# boardv2temperature.net
KiCad netlist of a schematic drawn in EAGLE
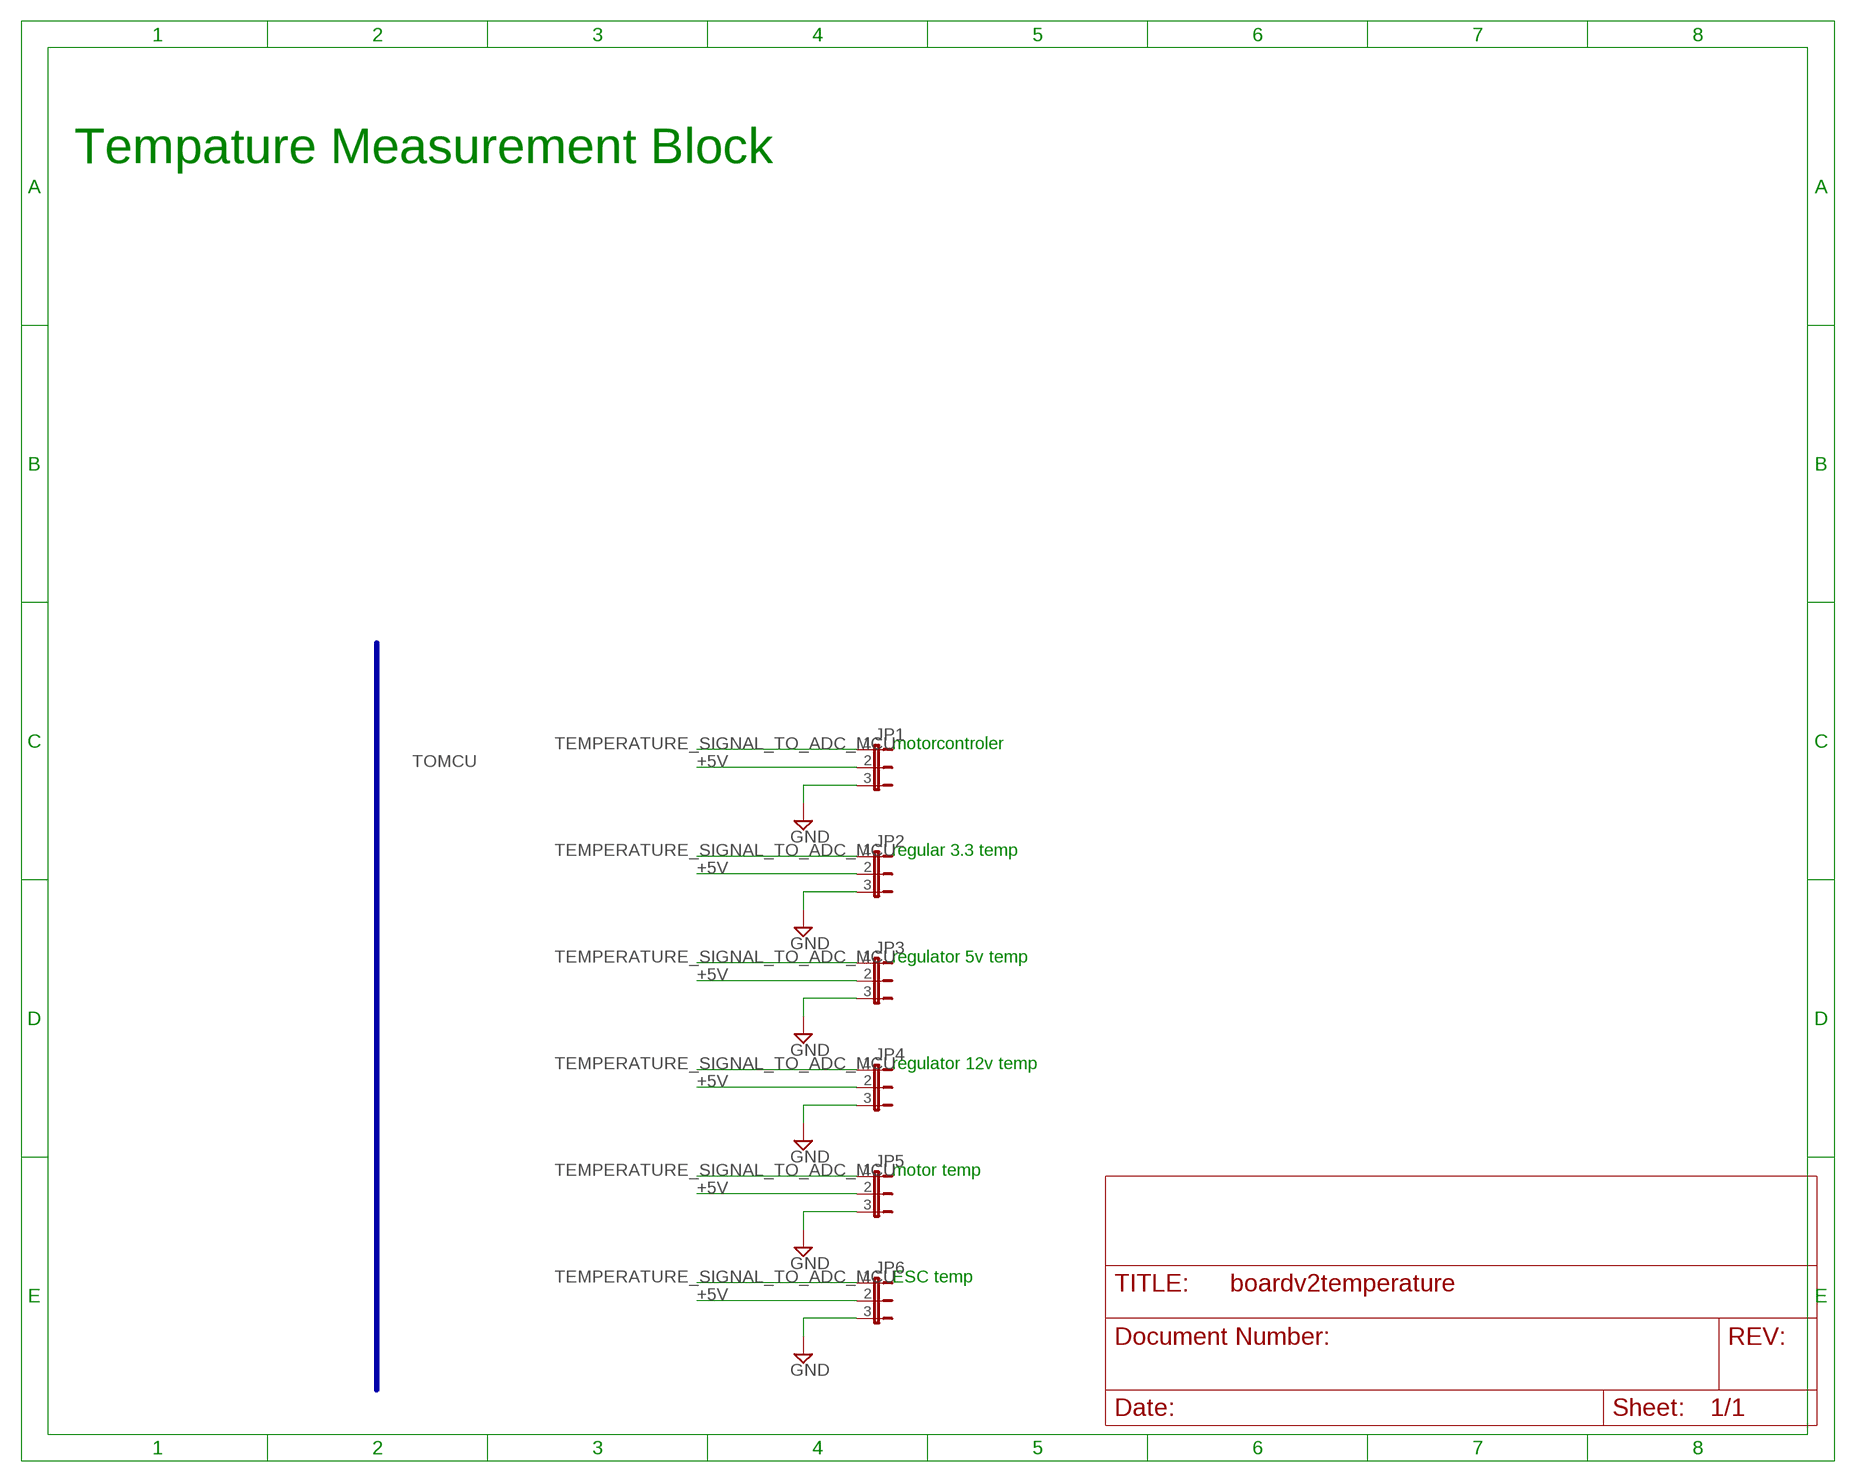
[diagram p0: schematic, sheet 1]

(export (version "E")
  (design (tool "Eeschema 10.0.6"))
  (components
    (comp (ref "JP1")
      (value "JP2E")
      (footprint "eagle-import:JP2")
      (libsource (lib "eagle-import") (part "JP2E"))
    )
    (comp (ref "JP2")
      (value "JP2E")
      (footprint "eagle-import:JP2")
      (libsource (lib "eagle-import") (part "JP2E"))
    )
    (comp (ref "JP3")
      (value "JP2E")
      (footprint "eagle-import:JP2")
      (libsource (lib "eagle-import") (part "JP2E"))
    )
    (comp (ref "JP4")
      (value "JP2E")
      (footprint "eagle-import:JP2")
      (libsource (lib "eagle-import") (part "JP2E"))
    )
    (comp (ref "JP5")
      (value "JP2E")
      (footprint "eagle-import:JP2")
      (libsource (lib "eagle-import") (part "JP2E"))
    )
    (comp (ref "JP6")
      (value "JP2E")
      (footprint "eagle-import:JP2")
      (libsource (lib "eagle-import") (part "JP2E"))
    )
  )
  (nets
    (net (code "2") (name "/+5V") (class "Default")
      (node (ref "JP1") (pin "2") (pinfunction "2_2") (pintype "passive"))
      (node (ref "JP2") (pin "2") (pinfunction "2_2") (pintype "passive"))
      (node (ref "JP3") (pin "2") (pinfunction "2_2") (pintype "passive"))
      (node (ref "JP4") (pin "2") (pinfunction "2_2") (pintype "passive"))
      (node (ref "JP5") (pin "2") (pinfunction "2_2") (pintype "passive"))
      (node (ref "JP6") (pin "2") (pinfunction "2_2") (pintype "passive"))
    )
    (net (code "3") (name "/TEMPERATURE_SIGNAL_TO_ADC_MCU") (class "Default")
      (node (ref "JP1") (pin "1") (pinfunction "1_1") (pintype "passive"))
      (node (ref "JP2") (pin "1") (pinfunction "1_1") (pintype "passive"))
      (node (ref "JP3") (pin "1") (pinfunction "1_1") (pintype "passive"))
      (node (ref "JP4") (pin "1") (pinfunction "1_1") (pintype "passive"))
      (node (ref "JP5") (pin "1") (pinfunction "1_1") (pintype "passive"))
      (node (ref "JP6") (pin "1") (pinfunction "1_1") (pintype "passive"))
    )
    (net (code "5") (name "GND") (class "Default")
      (node (ref "JP1") (pin "3") (pinfunction "3_3") (pintype "passive"))
      (node (ref "JP2") (pin "3") (pinfunction "3_3") (pintype "passive"))
      (node (ref "JP3") (pin "3") (pinfunction "3_3") (pintype "passive"))
      (node (ref "JP4") (pin "3") (pinfunction "3_3") (pintype "passive"))
      (node (ref "JP5") (pin "3") (pinfunction "3_3") (pintype "passive"))
      (node (ref "JP6") (pin "3") (pinfunction "3_3") (pintype "passive"))
    )
  )
)
